# LED_array_-_interface_v1_3.net
KiCad netlist of a schematic drawn in EAGLE
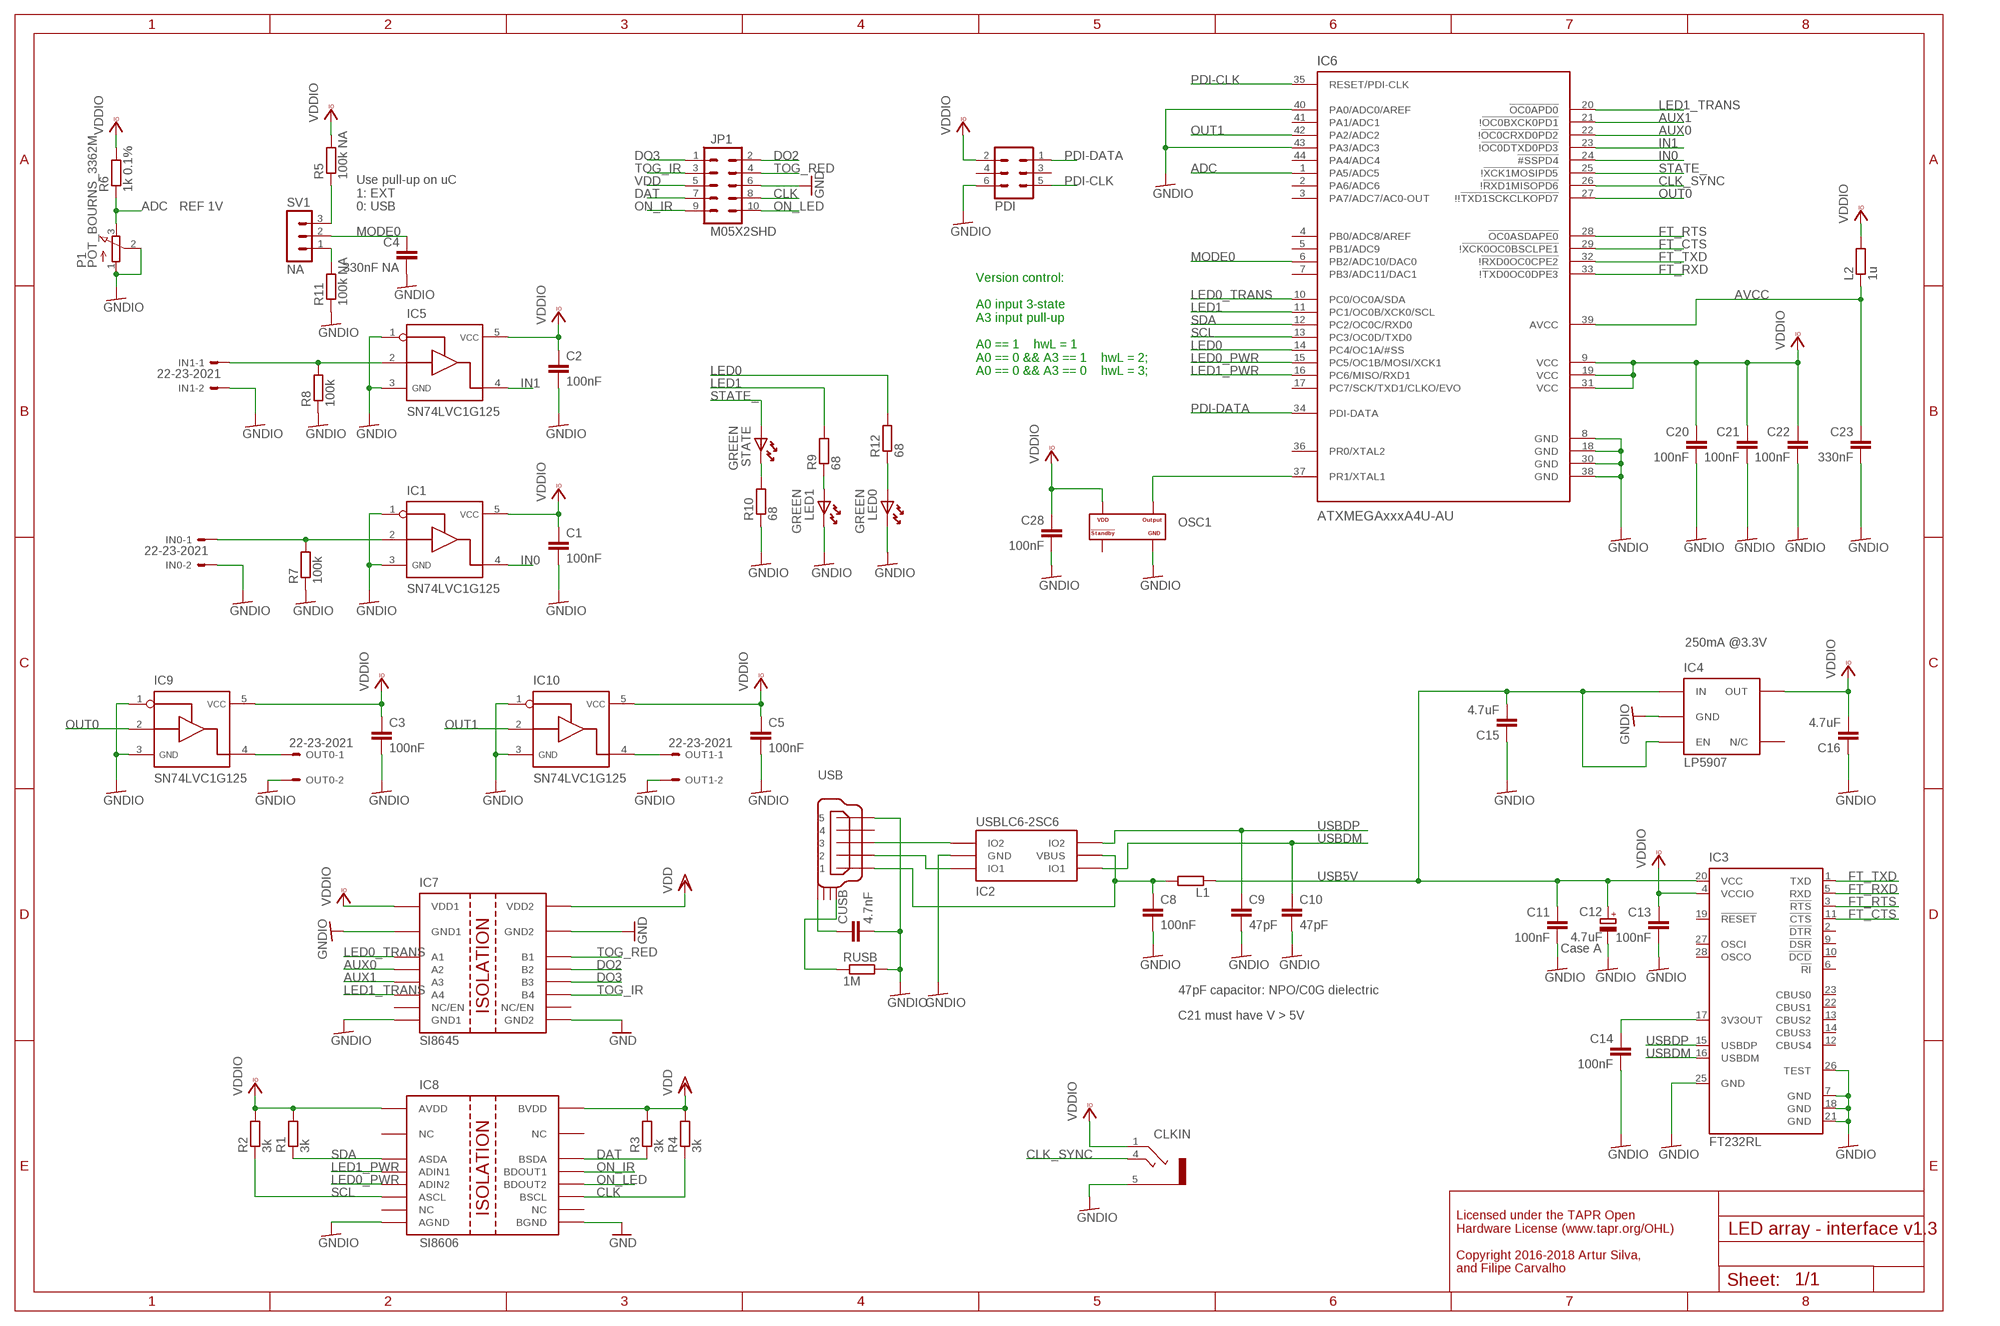
[diagram p0: schematic, sheet 1]

(export (version "E")
  (design (tool "Eeschema 10.0.6"))
  (components
    (comp (ref "C1")
      (value "100nF")
      (footprint "eagle-import:C0402")
      (libsource (lib "eagle-import") (part "C-EUC0402"))
    )
    (comp (ref "C2")
      (value "100nF")
      (footprint "eagle-import:C0402")
      (libsource (lib "eagle-import") (part "C-EUC0402"))
    )
    (comp (ref "C3")
      (value "100nF")
      (footprint "eagle-import:C0402")
      (libsource (lib "eagle-import") (part "C-EUC0402"))
    )
    (comp (ref "C4")
      (value "330nF NA")
      (footprint "eagle-import:C0402")
      (libsource (lib "eagle-import") (part "C-EUC0402"))
    )
    (comp (ref "C5")
      (value "100nF")
      (footprint "eagle-import:C0402")
      (libsource (lib "eagle-import") (part "C-EUC0402"))
    )
    (comp (ref "C8")
      (value "100nF")
      (footprint "eagle-import:C0402")
      (libsource (lib "eagle-import") (part "C-EUC0402"))
    )
    (comp (ref "C9")
      (value "47pF")
      (footprint "eagle-import:C0402")
      (libsource (lib "eagle-import") (part "C-EUC0402"))
    )
    (comp (ref "C10")
      (value "47pF")
      (footprint "eagle-import:C0402")
      (libsource (lib "eagle-import") (part "C-EUC0402"))
    )
    (comp (ref "C11")
      (value "100nF")
      (footprint "eagle-import:C0402")
      (libsource (lib "eagle-import") (part "C-EUC0402"))
    )
    (comp (ref "C12")
      (value "4.7uF")
      (footprint "eagle-import:A_3216-18W")
      (libsource (lib "eagle-import") (part "CPOL-EUA/3216-18W"))
    )
    (comp (ref "C13")
      (value "100nF")
      (footprint "eagle-import:C0402")
      (libsource (lib "eagle-import") (part "C-EUC0402"))
    )
    (comp (ref "C14")
      (value "100nF")
      (footprint "eagle-import:C0402")
      (libsource (lib "eagle-import") (part "C-EUC0402"))
    )
    (comp (ref "C15")
      (value "4.7uF")
      (footprint "eagle-import:C0402")
      (libsource (lib "eagle-import") (part "C-EUC0402"))
    )
    (comp (ref "C16")
      (value "4.7uF")
      (footprint "eagle-import:C0402")
      (libsource (lib "eagle-import") (part "C-EUC0402"))
    )
    (comp (ref "C20")
      (value "100nF")
      (footprint "eagle-import:C0402")
      (libsource (lib "eagle-import") (part "C-EUC0402"))
    )
    (comp (ref "C21")
      (value "100nF")
      (footprint "eagle-import:C0402")
      (libsource (lib "eagle-import") (part "C-EUC0402"))
    )
    (comp (ref "C22")
      (value "100nF")
      (footprint "eagle-import:C0402")
      (libsource (lib "eagle-import") (part "C-EUC0402"))
    )
    (comp (ref "C23")
      (value "330nF")
      (footprint "eagle-import:C0402")
      (libsource (lib "eagle-import") (part "C-EUC0402"))
    )
    (comp (ref "C28")
      (value "100nF")
      (footprint "eagle-import:C0402")
      (libsource (lib "eagle-import") (part "C-EUC0402"))
    )
    (comp (ref "CLKIN")
      (value "STEREO_JACK")
      (footprint "eagle-import:35RASMT2BHNTRX")
      (libsource (lib "eagle-import") (part "STEREO_JACK"))
    )
    (comp (ref "CUSB")
      (value "4.7nF")
      (footprint "eagle-import:C0402")
      (libsource (lib "eagle-import") (part "C-EUC0402"))
    )
    (comp (ref "IC1")
      (value "SN74LVC1G125")
      (footprint "eagle-import:SOT23-5")
      (libsource (lib "eagle-import") (part "SN74LVC1G125"))
    )
    (comp (ref "IC2")
      (value "USBLC6-2SC6")
      (footprint "eagle-import:SOT23-6L")
      (libsource (lib "eagle-import") (part "USBLC6-2"))
    )
    (comp (ref "IC3")
      (value "FT232RL")
      (footprint "eagle-import:SSOP28")
      (libsource (lib "eagle-import") (part "FT232RL"))
    )
    (comp (ref "IC4")
      (value "LP5907")
      (footprint "eagle-import:TSOT23-5")
      (libsource (lib "eagle-import") (part "TLV700XX"))
    )
    (comp (ref "IC5")
      (value "SN74LVC1G125")
      (footprint "eagle-import:SOT23-5")
      (libsource (lib "eagle-import") (part "SN74LVC1G125"))
    )
    (comp (ref "IC6")
      (value "ATXMEGAxxxA4U-AU")
      (footprint "eagle-import:QFP80P1200X1200X120-44N")
      (libsource (lib "eagle-import") (part "AT-XMEGA-XXA4-AU"))
    )
    (comp (ref "IC7")
      (value "SI8645")
      (footprint "eagle-import:NSOIC-16")
      (libsource (lib "eagle-import") (part "SI8645"))
    )
    (comp (ref "IC8")
      (value "SI8606")
      (footprint "eagle-import:NSOIC-16")
      (libsource (lib "eagle-import") (part "SI8606"))
    )
    (comp (ref "IC9")
      (value "SN74LVC1G125")
      (footprint "eagle-import:SOT23-5")
      (libsource (lib "eagle-import") (part "SN74LVC1G125"))
    )
    (comp (ref "IC10")
      (value "SN74LVC1G125")
      (footprint "eagle-import:SOT23-5")
      (libsource (lib "eagle-import") (part "SN74LVC1G125"))
    )
    (comp (ref "IN0")
      (value "22-23-2021")
      (footprint "eagle-import:22-23-2021")
      (fields (field (name "MF") "MOLEX"))
      (libsource (lib "eagle-import") (part "22-23-2021"))
    )
    (comp (ref "IN1")
      (value "22-23-2021")
      (footprint "eagle-import:22-23-2021")
      (fields (field (name "MF") "MOLEX"))
      (libsource (lib "eagle-import") (part "22-23-2021"))
    )
    (comp (ref "JP1")
      (value "M05X2SHD")
      (footprint "eagle-import:2X5-SHROUDED")
      (libsource (lib "eagle-import") (part "M05X2SHD"))
    )
    (comp (ref "L1")
      (value "???")
      (footprint "eagle-import:R0805")
      (libsource (lib "eagle-import") (part "R-EU_R0805"))
    )
    (comp (ref "L2")
      (value "1u")
      (footprint "eagle-import:R0805")
      (libsource (lib "eagle-import") (part "R-EU_R0805"))
    )
    (comp (ref "LED0")
      (value "GREEN")
      (footprint "eagle-import:LED_HAND")
      (libsource (lib "eagle-import") (part "LEDHAND"))
    )
    (comp (ref "LED1")
      (value "GREEN")
      (footprint "eagle-import:LED_HAND")
      (libsource (lib "eagle-import") (part "LEDHAND"))
    )
    (comp (ref "OSC1")
      (value "OSCILLATOR")
      (footprint "eagle-import:OSCILLATOR_3.2X2.5")
      (libsource (lib "eagle-import") (part "OSCILLATOR"))
    )
    (comp (ref "OUT0")
      (value "22-23-2021")
      (footprint "eagle-import:22-23-2021")
      (fields (field (name "MF") "MOLEX"))
      (libsource (lib "eagle-import") (part "22-23-2021"))
    )
    (comp (ref "OUT1")
      (value "22-23-2021")
      (footprint "eagle-import:22-23-2021")
      (fields (field (name "MF") "MOLEX"))
      (libsource (lib "eagle-import") (part "22-23-2021"))
    )
    (comp (ref "P1")
      (value "POT_BOURNS_3362M")
      (footprint "eagle-import:POT_BOURNS_3362M")
      (libsource (lib "eagle-import") (part "POT_BOURNS_3362M"))
    )
    (comp (ref "PDI")
      (value "MA03-2")
      (footprint "eagle-import:MA03-2")
      (libsource (lib "eagle-import") (part "MA03-2"))
    )
    (comp (ref "R1")
      (value "3k")
      (footprint "eagle-import:R0402")
      (libsource (lib "eagle-import") (part "R-EU_R0402"))
    )
    (comp (ref "R2")
      (value "3k")
      (footprint "eagle-import:R0402")
      (libsource (lib "eagle-import") (part "R-EU_R0402"))
    )
    (comp (ref "R3")
      (value "3k")
      (footprint "eagle-import:R0402")
      (libsource (lib "eagle-import") (part "R-EU_R0402"))
    )
    (comp (ref "R4")
      (value "3k")
      (footprint "eagle-import:R0402")
      (libsource (lib "eagle-import") (part "R-EU_R0402"))
    )
    (comp (ref "R5")
      (value "100k NA")
      (footprint "eagle-import:R0402")
      (libsource (lib "eagle-import") (part "R-EU_R0402"))
    )
    (comp (ref "R6")
      (value "1k 0.1%")
      (footprint "eagle-import:R0402")
      (libsource (lib "eagle-import") (part "R-EU_R0402"))
    )
    (comp (ref "R7")
      (value "100k")
      (footprint "eagle-import:R0402")
      (libsource (lib "eagle-import") (part "R-EU_R0402"))
    )
    (comp (ref "R8")
      (value "100k")
      (footprint "eagle-import:R0402")
      (libsource (lib "eagle-import") (part "R-EU_R0402"))
    )
    (comp (ref "R9")
      (value "68")
      (footprint "eagle-import:R0402")
      (libsource (lib "eagle-import") (part "R-EU_R0402"))
    )
    (comp (ref "R10")
      (value "68")
      (footprint "eagle-import:R0402")
      (libsource (lib "eagle-import") (part "R-EU_R0402"))
    )
    (comp (ref "R11")
      (value "100k NA")
      (footprint "eagle-import:R0402")
      (libsource (lib "eagle-import") (part "R-EU_R0402"))
    )
    (comp (ref "R12")
      (value "68")
      (footprint "eagle-import:R0402")
      (libsource (lib "eagle-import") (part "R-EU_R0402"))
    )
    (comp (ref "RUSB")
      (value "1M")
      (footprint "eagle-import:R0603")
      (libsource (lib "eagle-import") (part "R-EU_R0603"))
    )
    (comp (ref "STATE")
      (value "GREEN")
      (footprint "eagle-import:LED_HAND")
      (libsource (lib "eagle-import") (part "LEDHAND"))
    )
    (comp (ref "SV1")
      (value "NA")
      (footprint "eagle-import:MA03-1")
      (libsource (lib "eagle-import") (part "MA03-1"))
    )
    (comp (ref "USB")
      (value "USB_MINI_B")
      (footprint "eagle-import:240-0002-1")
      (libsource (lib "eagle-import") (part "USB_MINI_B"))
    )
  )
  (nets
    (net (code "1") (name "/ADC") (class "Default")
      (node (ref "IC6") (pin "1") (pinfunction "PA5/ADC5_1") (pintype "bidirectional"))
      (node (ref "P1") (pin "3") (pinfunction "E_3") (pintype "passive"))
      (node (ref "R6") (pin "1") (pinfunction "1_1") (pintype "passive"))
    )
    (net (code "2") (name "/AUX0") (class "Default")
      (node (ref "IC6") (pin "22") (pinfunction "~OC0CRXD0PD2_22") (pintype "bidirectional"))
      (node (ref "IC7") (pin "4") (pinfunction "A2_4") (pintype "bidirectional"))
    )
    (net (code "3") (name "/AUX1") (class "Default")
      (node (ref "IC6") (pin "21") (pinfunction "~OC0BXCK0PD1_21") (pintype "bidirectional"))
      (node (ref "IC7") (pin "5") (pinfunction "A3_5") (pintype "bidirectional"))
    )
    (net (code "4") (name "/AVCC") (class "Default")
      (node (ref "C23") (pin "1") (pinfunction "1_1") (pintype "passive"))
      (node (ref "IC6") (pin "39") (pinfunction "AVCC_39") (pintype "power_in"))
      (node (ref "L2") (pin "1") (pinfunction "1_1") (pintype "passive"))
    )
    (net (code "5") (name "/CLK") (class "Default")
      (node (ref "IC8") (pin "11") (pinfunction "BSCL_11") (pintype "bidirectional"))
      (node (ref "JP1") (pin "8") (pinfunction "8_8") (pintype "passive"))
      (node (ref "R4") (pin "1") (pinfunction "1_1") (pintype "passive"))
    )
    (net (code "6") (name "/CLK_SYNC") (class "Default")
      (node (ref "CLKIN") (pin "4") (pinfunction "4_4") (pintype "passive"))
      (node (ref "IC6") (pin "26") (pinfunction "~RXD1MISOPD6_26") (pintype "bidirectional"))
    )
    (net (code "7") (name "/DAT") (class "Default")
      (node (ref "IC8") (pin "14") (pinfunction "BSDA_14") (pintype "bidirectional"))
      (node (ref "JP1") (pin "7") (pinfunction "7_7") (pintype "passive"))
      (node (ref "R3") (pin "1") (pinfunction "1_1") (pintype "passive"))
    )
    (net (code "8") (name "/DO2") (class "Default")
      (node (ref "IC7") (pin "13") (pinfunction "B2_13") (pintype "bidirectional"))
      (node (ref "JP1") (pin "2") (pinfunction "2_2") (pintype "passive"))
    )
    (net (code "9") (name "/DO3") (class "Default")
      (node (ref "IC7") (pin "12") (pinfunction "B3_12") (pintype "bidirectional"))
      (node (ref "JP1") (pin "1") (pinfunction "1_1") (pintype "passive"))
    )
    (net (code "10") (name "/FT_CTS") (class "Default")
      (node (ref "IC3") (pin "11") (pinfunction "~{CTS}_11") (pintype "input"))
      (node (ref "IC6") (pin "29") (pinfunction "~XCK0OC0BSCLPE1_29") (pintype "bidirectional"))
    )
    (net (code "11") (name "/FT_RTS") (class "Default")
      (node (ref "IC3") (pin "3") (pinfunction "~{RTS}_3") (pintype "output"))
      (node (ref "IC6") (pin "28") (pinfunction "~{OC0ASDAPE0}_28") (pintype "bidirectional"))
    )
    (net (code "12") (name "/FT_RXD") (class "Default")
      (node (ref "IC3") (pin "5") (pinfunction "RXD_5") (pintype "input"))
      (node (ref "IC6") (pin "33") (pinfunction "~TXD0OC0DPE3_33") (pintype "bidirectional"))
    )
    (net (code "13") (name "/FT_TXD") (class "Default")
      (node (ref "IC3") (pin "1") (pinfunction "TXD_1") (pintype "output"))
      (node (ref "IC6") (pin "32") (pinfunction "~RXD0OC0CPE2_32") (pintype "bidirectional"))
    )
    (net (code "14") (name "/IN0") (class "Default")
      (node (ref "IC1") (pin "4") (pinfunction "P$4_4") (pintype "bidirectional"))
      (node (ref "IC6") (pin "24") (pinfunction "~{#SSPD4}_24") (pintype "bidirectional"))
    )
    (net (code "15") (name "/IN1") (class "Default")
      (node (ref "IC5") (pin "4") (pinfunction "P$4_4") (pintype "bidirectional"))
      (node (ref "IC6") (pin "23") (pinfunction "~OC0DTXD0PD3_23") (pintype "bidirectional"))
    )
    (net (code "16") (name "/LED0") (class "Default")
      (node (ref "IC6") (pin "14") (pinfunction "PC4/OC1A/#SS_14") (pintype "bidirectional"))
      (node (ref "R12") (pin "2") (pinfunction "2_2") (pintype "passive"))
    )
    (net (code "17") (name "/LED0_PWR") (class "Default")
      (node (ref "IC6") (pin "15") (pinfunction "PC5/OC1B/MOSI/XCK1_15") (pintype "bidirectional"))
      (node (ref "IC8") (pin "5") (pinfunction "ADIN2_5") (pintype "bidirectional"))
    )
    (net (code "18") (name "/LED0_TRANS") (class "Default")
      (node (ref "IC6") (pin "10") (pinfunction "PC0/OC0A/SDA_10") (pintype "bidirectional"))
      (node (ref "IC7") (pin "3") (pinfunction "A1_3") (pintype "bidirectional"))
    )
    (net (code "19") (name "/LED1") (class "Default")
      (node (ref "IC6") (pin "11") (pinfunction "PC1/OC0B/XCK0/SCL_11") (pintype "bidirectional"))
      (node (ref "R9") (pin "2") (pinfunction "2_2") (pintype "passive"))
    )
    (net (code "20") (name "/LED1_PWR") (class "Default")
      (node (ref "IC6") (pin "16") (pinfunction "PC6/MISO/RXD1_16") (pintype "bidirectional"))
      (node (ref "IC8") (pin "4") (pinfunction "ADIN1_4") (pintype "bidirectional"))
    )
    (net (code "21") (name "/LED1_TRANS") (class "Default")
      (node (ref "IC6") (pin "20") (pinfunction "~{OC0APD0}_20") (pintype "bidirectional"))
      (node (ref "IC7") (pin "6") (pinfunction "A4_6") (pintype "bidirectional"))
    )
    (net (code "22") (name "/MODE0") (class "Default")
      (node (ref "C4") (pin "1") (pinfunction "1_1") (pintype "passive"))
      (node (ref "IC6") (pin "6") (pinfunction "PB2/ADC10/DAC0_6") (pintype "bidirectional"))
      (node (ref "SV1") (pin "2") (pinfunction "2_2") (pintype "passive"))
    )
    (net (code "23") (name "/ON_IR") (class "Default")
      (node (ref "IC8") (pin "13") (pinfunction "BDOUT1_13") (pintype "bidirectional"))
      (node (ref "JP1") (pin "9") (pinfunction "9_9") (pintype "passive"))
    )
    (net (code "24") (name "/ON_LED") (class "Default")
      (node (ref "IC8") (pin "12") (pinfunction "BDOUT2_12") (pintype "bidirectional"))
      (node (ref "JP1") (pin "10") (pinfunction "10_10") (pintype "passive"))
    )
    (net (code "25") (name "/OUT0") (class "Default")
      (node (ref "IC6") (pin "27") (pinfunction "~~{TXD1SCKCLKOPD7}_27") (pintype "bidirectional"))
      (node (ref "IC9") (pin "2") (pinfunction "P$2_2") (pintype "bidirectional"))
    )
    (net (code "26") (name "/OUT1") (class "Default")
      (node (ref "IC10") (pin "2") (pinfunction "P$2_2") (pintype "bidirectional"))
      (node (ref "IC6") (pin "42") (pinfunction "PA2/ADC2_42") (pintype "bidirectional"))
    )
    (net (code "27") (name "/PDI-CLK") (class "Default")
      (node (ref "IC6") (pin "35") (pinfunction "RESET/PDI-CLK_35") (pintype "input"))
      (node (ref "PDI") (pin "5") (pinfunction "5_5") (pintype "passive"))
    )
    (net (code "28") (name "/PDI-DATA") (class "Default")
      (node (ref "IC6") (pin "34") (pinfunction "PDI-DATA_34") (pintype "bidirectional"))
      (node (ref "PDI") (pin "1") (pinfunction "1_1") (pintype "passive"))
    )
    (net (code "29") (name "/SCL") (class "Default")
      (node (ref "IC6") (pin "13") (pinfunction "PC3/OC0D/TXD0_13") (pintype "bidirectional"))
      (node (ref "IC8") (pin "6") (pinfunction "ASCL_6") (pintype "bidirectional"))
      (node (ref "R2") (pin "1") (pinfunction "1_1") (pintype "passive"))
    )
    (net (code "30") (name "/SDA") (class "Default")
      (node (ref "IC6") (pin "12") (pinfunction "PC2/OC0C/RXD0_12") (pintype "bidirectional"))
      (node (ref "IC8") (pin "3") (pinfunction "ASDA_3") (pintype "bidirectional"))
      (node (ref "R1") (pin "1") (pinfunction "1_1") (pintype "passive"))
    )
    (net (code "31") (name "/STATE_") (class "Default")
      (node (ref "IC6") (pin "25") (pinfunction "~XCK1MOSIPD5_25") (pintype "bidirectional"))
      (node (ref "STATE") (pin "A") (pinfunction "A_A") (pintype "bidirectional"))
    )
    (net (code "32") (name "/TOG_IR") (class "Default")
      (node (ref "IC7") (pin "11") (pinfunction "B4_11") (pintype "bidirectional"))
      (node (ref "JP1") (pin "3") (pinfunction "3_3") (pintype "passive"))
    )
    (net (code "33") (name "/TOG_RED") (class "Default")
      (node (ref "IC7") (pin "14") (pinfunction "B1_14") (pintype "bidirectional"))
      (node (ref "JP1") (pin "4") (pinfunction "4_4") (pintype "passive"))
    )
    (net (code "34") (name "/USB5V") (class "Default")
      (node (ref "C11") (pin "1") (pinfunction "1_1") (pintype "passive"))
      (node (ref "C12") (pin "+") (pinfunction "+_+") (pintype "passive"))
      (node (ref "C15") (pin "2") (pinfunction "2_2") (pintype "passive"))
      (node (ref "IC3") (pin "20") (pinfunction "VCC_20") (pintype "power_in"))
      (node (ref "IC4") (pin "1") (pinfunction "IN_1") (pintype "bidirectional"))
      (node (ref "IC4") (pin "3") (pinfunction "EN_3") (pintype "bidirectional"))
      (node (ref "L1") (pin "1") (pinfunction "1_1") (pintype "passive"))
    )
    (net (code "35") (name "/USBDM") (class "Default")
      (node (ref "C10") (pin "1") (pinfunction "1_1") (pintype "passive"))
      (node (ref "IC2") (pin "P$6") (pinfunction "IO1_P$6") (pintype "bidirectional"))
      (node (ref "IC3") (pin "16") (pinfunction "USBDM_16") (pintype "bidirectional"))
    )
    (net (code "36") (name "/USBDP") (class "Default")
      (node (ref "C9") (pin "1") (pinfunction "1_1") (pintype "passive"))
      (node (ref "IC2") (pin "P$4") (pinfunction "IO2_P$4") (pintype "bidirectional"))
      (node (ref "IC3") (pin "15") (pinfunction "USBDP_15") (pintype "bidirectional"))
    )
    (net (code "37") (name "GND") (class "Default")
      (node (ref "IC7") (pin "15") (pinfunction "GND2_15") (pintype "bidirectional"))
      (node (ref "IC7") (pin "9") (pinfunction "GND2_9") (pintype "bidirectional"))
      (node (ref "IC8") (pin "9") (pinfunction "BGND_9") (pintype "bidirectional"))
      (node (ref "JP1") (pin "6") (pinfunction "6_6") (pintype "passive"))
    )
    (net (code "38") (name "GNDIO") (class "Default")
      (node (ref "C1") (pin "2") (pinfunction "2_2") (pintype "passive"))
      (node (ref "C10") (pin "2") (pinfunction "2_2") (pintype "passive"))
      (node (ref "C11") (pin "2") (pinfunction "2_2") (pintype "passive"))
      (node (ref "C12") (pin "-") (pinfunction "-_-") (pintype "passive"))
      (node (ref "C13") (pin "2") (pinfunction "2_2") (pintype "passive"))
      (node (ref "C14") (pin "2") (pinfunction "2_2") (pintype "passive"))
      (node (ref "C15") (pin "1") (pinfunction "1_1") (pintype "passive"))
      (node (ref "C16") (pin "1") (pinfunction "1_1") (pintype "passive"))
      (node (ref "C2") (pin "2") (pinfunction "2_2") (pintype "passive"))
      (node (ref "C20") (pin "2") (pinfunction "2_2") (pintype "passive"))
      (node (ref "C21") (pin "2") (pinfunction "2_2") (pintype "passive"))
      (node (ref "C22") (pin "2") (pinfunction "2_2") (pintype "passive"))
      (node (ref "C23") (pin "2") (pinfunction "2_2") (pintype "passive"))
      (node (ref "C28") (pin "2") (pinfunction "2_2") (pintype "passive"))
      (node (ref "C3") (pin "2") (pinfunction "2_2") (pintype "passive"))
      (node (ref "C4") (pin "2") (pinfunction "2_2") (pintype "passive"))
      (node (ref "C5") (pin "2") (pinfunction "2_2") (pintype "passive"))
      (node (ref "C8") (pin "2") (pinfunction "2_2") (pintype "passive"))
      (node (ref "C9") (pin "2") (pinfunction "2_2") (pintype "passive"))
      (node (ref "CLKIN") (pin "5") (pinfunction "5_5") (pintype "passive"))
      (node (ref "CUSB") (pin "2") (pinfunction "2_2") (pintype "passive"))
      (node (ref "IC1") (pin "1") (pinfunction "P$1_1") (pintype "bidirectional"))
      (node (ref "IC1") (pin "3") (pinfunction "P$3_3") (pintype "bidirectional"))
      (node (ref "IC10") (pin "1") (pinfunction "P$1_1") (pintype "bidirectional"))
      (node (ref "IC10") (pin "3") (pinfunction "P$3_3") (pintype "bidirectional"))
      (node (ref "IC2") (pin "P$2") (pinfunction "GND_P$2") (pintype "bidirectional"))
      (node (ref "IC3") (pin "18") (pinfunction "GND_18") (pintype "power_in"))
      (node (ref "IC3") (pin "21") (pinfunction "GND_21") (pintype "power_in"))
      (node (ref "IC3") (pin "25") (pinfunction "GND_25") (pintype "power_in"))
      (node (ref "IC3") (pin "26") (pinfunction "TEST_26") (pintype "input"))
      (node (ref "IC3") (pin "7") (pinfunction "GND_7") (pintype "power_in"))
      (node (ref "IC4") (pin "2") (pinfunction "GND_2") (pintype "bidirectional"))
      (node (ref "IC5") (pin "1") (pinfunction "P$1_1") (pintype "bidirectional"))
      (node (ref "IC5") (pin "3") (pinfunction "P$3_3") (pintype "bidirectional"))
      (node (ref "IC6") (pin "18") (pinfunction "GND_18") (pintype "power_in"))
      (node (ref "IC6") (pin "30") (pinfunction "GND_30") (pintype "power_in"))
      (node (ref "IC6") (pin "38") (pinfunction "GND_38") (pintype "power_in"))
      (node (ref "IC6") (pin "40") (pinfunction "PA0/ADC0/AREF_40") (pintype "bidirectional"))
      (node (ref "IC6") (pin "43") (pinfunction "PA3/ADC3_43") (pintype "bidirectional"))
      (node (ref "IC6") (pin "8") (pinfunction "GND_8") (pintype "power_in"))
      (node (ref "IC7") (pin "2") (pinfunction "GND1_2") (pintype "bidirectional"))
      (node (ref "IC7") (pin "8") (pinfunction "GND1_8") (pintype "bidirectional"))
      (node (ref "IC8") (pin "8") (pinfunction "AGND_8") (pintype "bidirectional"))
      (node (ref "IC9") (pin "1") (pinfunction "P$1_1") (pintype "bidirectional"))
      (node (ref "IC9") (pin "3") (pinfunction "P$3_3") (pintype "bidirectional"))
      (node (ref "IN0") (pin "2") (pinfunction "S_2") (pintype "passive"))
      (node (ref "IN1") (pin "2") (pinfunction "S_2") (pintype "passive"))
      (node (ref "LED0") (pin "K") (pinfunction "K_K") (pintype "bidirectional"))
      (node (ref "LED1") (pin "K") (pinfunction "K_K") (pintype "bidirectional"))
      (node (ref "OSC1") (pin "P$2") (pinfunction "GND_P$2") (pintype "passive"))
      (node (ref "OUT0") (pin "2") (pinfunction "S_2") (pintype "passive"))
      (node (ref "OUT1") (pin "2") (pinfunction "S_2") (pintype "passive"))
      (node (ref "P1") (pin "1") (pinfunction "A_1") (pintype "passive"))
      (node (ref "P1") (pin "2") (pinfunction "S_2") (pintype "passive"))
      (node (ref "PDI") (pin "6") (pinfunction "6_6") (pintype "passive"))
      (node (ref "R10") (pin "1") (pinfunction "1_1") (pintype "passive"))
      (node (ref "R11") (pin "1") (pinfunction "1_1") (pintype "passive"))
      (node (ref "R7") (pin "1") (pinfunction "1_1") (pintype "passive"))
      (node (ref "R8") (pin "1") (pinfunction "1_1") (pintype "passive"))
      (node (ref "RUSB") (pin "2") (pinfunction "2_2") (pintype "passive"))
      (node (ref "USB") (pin "P$5") (pinfunction "5_P$5") (pintype "bidirectional"))
    )
    (net (code "39") (name "Net-(IC1-P$2)") (class "Default")
      (node (ref "IC1") (pin "2") (pinfunction "P$2_2") (pintype "bidirectional"))
      (node (ref "IN0") (pin "1") (pinfunction "S_1") (pintype "passive"))
      (node (ref "R7") (pin "2") (pinfunction "2_2") (pintype "passive"))
    )
    (net (code "40") (name "Net-(IC2-VBUS)") (class "Default")
      (node (ref "C8") (pin "1") (pinfunction "1_1") (pintype "passive"))
      (node (ref "IC2") (pin "P$5") (pinfunction "VBUS_P$5") (pintype "bidirectional"))
      (node (ref "L1") (pin "2") (pinfunction "2_2") (pintype "passive"))
      (node (ref "USB") (pin "P$1") (pinfunction "1_P$1") (pintype "bidirectional"))
    )
    (net (code "41") (name "Net-(IC3-3V3OUT)") (class "Default")
      (node (ref "C14") (pin "1") (pinfunction "1_1") (pintype "passive"))
      (node (ref "IC3") (pin "17") (pinfunction "3V3OUT_17") (pintype "output"))
    )
    (net (code "42") (name "Net-(IC5-P$2)") (class "Default")
      (node (ref "IC5") (pin "2") (pinfunction "P$2_2") (pintype "bidirectional"))
      (node (ref "IN1") (pin "1") (pinfunction "S_1") (pintype "passive"))
      (node (ref "R8") (pin "2") (pinfunction "2_2") (pintype "passive"))
    )
    (net (code "43") (name "Net-(IC6-PR1{slash}XTAL1)") (class "Default")
      (node (ref "IC6") (pin "37") (pinfunction "PR1/XTAL1_37") (pintype "bidirectional"))
      (node (ref "OSC1") (pin "P$3") (pinfunction "OUTPUT_P$3") (pintype "passive"))
    )
    (net (code "44") (name "Net-(IC9-P$4)") (class "Default")
      (node (ref "IC9") (pin "4") (pinfunction "P$4_4") (pintype "bidirectional"))
      (node (ref "OUT0") (pin "1") (pinfunction "S_1") (pintype "passive"))
    )
    (net (code "45") (name "Net-(IC10-P$4)") (class "Default")
      (node (ref "IC10") (pin "4") (pinfunction "P$4_4") (pintype "bidirectional"))
      (node (ref "OUT1") (pin "1") (pinfunction "S_1") (pintype "passive"))
    )
    (net (code "46") (name "Net-(LED0-PadA)") (class "Default")
      (node (ref "LED0") (pin "A") (pinfunction "A_A") (pintype "bidirectional"))
      (node (ref "R12") (pin "1") (pinfunction "1_1") (pintype "passive"))
    )
    (net (code "47") (name "Net-(LED1-PadA)") (class "Default")
      (node (ref "LED1") (pin "A") (pinfunction "A_A") (pintype "bidirectional"))
      (node (ref "R9") (pin "1") (pinfunction "1_1") (pintype "passive"))
    )
    (net (code "48") (name "Net-(R5-Pad1)") (class "Default")
      (node (ref "R5") (pin "1") (pinfunction "1_1") (pintype "passive"))
      (node (ref "SV1") (pin "3") (pinfunction "3_3") (pintype "passive"))
    )
    (net (code "49") (name "Net-(R10-Pad2)") (class "Default")
      (node (ref "R10") (pin "2") (pinfunction "2_2") (pintype "passive"))
      (node (ref "STATE") (pin "K") (pinfunction "K_K") (pintype "bidirectional"))
    )
    (net (code "50") (name "Net-(R11-Pad2)") (class "Default")
      (node (ref "R11") (pin "2") (pinfunction "2_2") (pintype "passive"))
      (node (ref "SV1") (pin "1") (pinfunction "1_1") (pintype "passive"))
    )
    (net (code "51") (name "Net-(USB-2)") (class "Default")
      (node (ref "IC2") (pin "P$1") (pinfunction "IO1_P$1") (pintype "bidirectional"))
      (node (ref "USB") (pin "P$2") (pinfunction "2_P$2") (pintype "bidirectional"))
    )
    (net (code "52") (name "Net-(USB-3)") (class "Default")
      (node (ref "IC2") (pin "P$3") (pinfunction "IO2_P$3") (pintype "bidirectional"))
      (node (ref "USB") (pin "P$3") (pinfunction "3_P$3") (pintype "bidirectional"))
    )
    (net (code "53") (name "Net-(USB-P$1)") (class "Default")
      (node (ref "RUSB") (pin "1") (pinfunction "1_1") (pintype "passive"))
      (node (ref "USB") (pin "SHIELD_1") (pinfunction "P$1_SHIELD_1") (pintype "bidirectional"))
    )
    (net (code "54") (name "Net-(USB-P$4)") (class "Default")
      (node (ref "CUSB") (pin "1") (pinfunction "1_1") (pintype "passive"))
      (node (ref "USB") (pin "SHIELD_4") (pinfunction "P$4_SHIELD_4") (pintype "bidirectional"))
    )
    (net (code "55") (name "VDD") (class "Default")
      (node (ref "IC7") (pin "16") (pinfunction "VDD2_16") (pintype "bidirectional"))
      (node (ref "IC8") (pin "16") (pinfunction "BVDD_16") (pintype "bidirectional"))
      (node (ref "JP1") (pin "5") (pinfunction "5_5") (pintype "passive"))
      (node (ref "R3") (pin "2") (pinfunction "2_2") (pintype "passive"))
      (node (ref "R4") (pin "2") (pinfunction "2_2") (pintype "passive"))
    )
    (net (code "56") (name "VDDIO") (class "Default")
      (node (ref "C1") (pin "1") (pinfunction "1_1") (pintype "passive"))
      (node (ref "C13") (pin "1") (pinfunction "1_1") (pintype "passive"))
      (node (ref "C16") (pin "2") (pinfunction "2_2") (pintype "passive"))
      (node (ref "C2") (pin "1") (pinfunction "1_1") (pintype "passive"))
      (node (ref "C20") (pin "1") (pinfunction "1_1") (pintype "passive"))
      (node (ref "C21") (pin "1") (pinfunction "1_1") (pintype "passive"))
      (node (ref "C22") (pin "1") (pinfunction "1_1") (pintype "passive"))
      (node (ref "C28") (pin "1") (pinfunction "1_1") (pintype "passive"))
      (node (ref "C3") (pin "1") (pinfunction "1_1") (pintype "passive"))
      (node (ref "C5") (pin "1") (pinfunction "1_1") (pintype "passive"))
      (node (ref "CLKIN") (pin "1") (pinfunction "1_1") (pintype "passive"))
      (node (ref "IC1") (pin "5") (pinfunction "P$5_5") (pintype "bidirectional"))
      (node (ref "IC10") (pin "5") (pinfunction "P$5_5") (pintype "bidirectional"))
      (node (ref "IC3") (pin "4") (pinfunction "VCCIO_4") (pintype "power_in"))
      (node (ref "IC4") (pin "5") (pinfunction "OUT_5") (pintype "bidirectional"))
      (node (ref "IC5") (pin "5") (pinfunction "P$5_5") (pintype "bidirectional"))
      (node (ref "IC6") (pin "19") (pinfunction "VCC_19") (pintype "power_in"))
      (node (ref "IC6") (pin "31") (pinfunction "VCC_31") (pintype "power_in"))
      (node (ref "IC6") (pin "9") (pinfunction "VCC_9") (pintype "power_in"))
      (node (ref "IC7") (pin "1") (pinfunction "VDD1_1") (pintype "bidirectional"))
      (node (ref "IC8") (pin "1") (pinfunction "AVDD_1") (pintype "bidirectional"))
      (node (ref "IC9") (pin "5") (pinfunction "P$5_5") (pintype "bidirectional"))
      (node (ref "L2") (pin "2") (pinfunction "2_2") (pintype "passive"))
      (node (ref "OSC1") (pin "P$4") (pinfunction "VDD_P$4") (pintype "passive"))
      (node (ref "PDI") (pin "2") (pinfunction "2_2") (pintype "passive"))
      (node (ref "R1") (pin "2") (pinfunction "2_2") (pintype "passive"))
      (node (ref "R2") (pin "2") (pinfunction "2_2") (pintype "passive"))
      (node (ref "R5") (pin "2") (pinfunction "2_2") (pintype "passive"))
      (node (ref "R6") (pin "2") (pinfunction "2_2") (pintype "passive"))
    )
    (net (code "57") (name "unconnected-(IC3-CBUS0-Pad23)") (class "Default")
      (node (ref "IC3") (pin "23") (pinfunction "CBUS0_23") (pintype "bidirectional"))
    )
    (net (code "58") (name "unconnected-(IC3-CBUS1-Pad22)") (class "Default")
      (node (ref "IC3") (pin "22") (pinfunction "CBUS1_22") (pintype "bidirectional"))
    )
    (net (code "59") (name "unconnected-(IC3-CBUS2-Pad13)") (class "Default")
      (node (ref "IC3") (pin "13") (pinfunction "CBUS2_13") (pintype "bidirectional"))
    )
    (net (code "60") (name "unconnected-(IC3-CBUS3-Pad14)") (class "Default")
      (node (ref "IC3") (pin "14") (pinfunction "CBUS3_14") (pintype "bidirectional"))
    )
    (net (code "61") (name "unconnected-(IC3-CBUS4-Pad12)") (class "Default")
      (node (ref "IC3") (pin "12") (pinfunction "CBUS4_12") (pintype "bidirectional"))
    )
    (net (code "62") (name "unconnected-(IC3-OSCI-Pad27)") (class "Default")
      (node (ref "IC3") (pin "27") (pinfunction "OSCI_27") (pintype "input"))
    )
    (net (code "63") (name "unconnected-(IC3-OSCO-Pad28)") (class "Default")
      (node (ref "IC3") (pin "28") (pinfunction "OSCO_28") (pintype "output"))
    )
    (net (code "64") (name "unconnected-(IC3-~{DCD}-Pad10)") (class "Default")
      (node (ref "IC3") (pin "10") (pinfunction "~{DCD}_10") (pintype "input"))
    )
    (net (code "65") (name "unconnected-(IC3-~{DSR}-Pad9)") (class "Default")
      (node (ref "IC3") (pin "9") (pinfunction "~{DSR}_9") (pintype "input"))
    )
    (net (code "66") (name "unconnected-(IC3-~{DTR}-Pad2)") (class "Default")
      (node (ref "IC3") (pin "2") (pinfunction "~{DTR}_2") (pintype "output"))
    )
    (net (code "67") (name "unconnected-(IC3-~{RESET}-Pad19)") (class "Default")
      (node (ref "IC3") (pin "19") (pinfunction "~{RESET}_19") (pintype "input"))
    )
    (net (code "68") (name "unconnected-(IC3-~{RI}-Pad6)") (class "Default")
      (node (ref "IC3") (pin "6") (pinfunction "~{RI}_6") (pintype "input"))
    )
    (net (code "69") (name "unconnected-(IC4-N{slash}C-Pad4)") (class "Default")
      (node (ref "IC4") (pin "4") (pinfunction "N/C_4") (pintype "bidirectional"))
    )
    (net (code "70") (name "unconnected-(IC6-PA1{slash}ADC1-Pad41)") (class "Default")
      (node (ref "IC6") (pin "41") (pinfunction "PA1/ADC1_41") (pintype "bidirectional"))
    )
    (net (code "71") (name "unconnected-(IC6-PA4{slash}ADC4-Pad44)") (class "Default")
      (node (ref "IC6") (pin "44") (pinfunction "PA4/ADC4_44") (pintype "bidirectional"))
    )
    (net (code "72") (name "unconnected-(IC6-PA6{slash}ADC6-Pad2)") (class "Default")
      (node (ref "IC6") (pin "2") (pinfunction "PA6/ADC6_2") (pintype "bidirectional"))
    )
    (net (code "73") (name "unconnected-(IC6-PA7{slash}ADC7{slash}AC0-OUT-Pad3)") (class "Default")
      (node (ref "IC6") (pin "3") (pinfunction "PA7/ADC7/AC0-OUT_3") (pintype "bidirectional"))
    )
    (net (code "74") (name "unconnected-(IC6-PB0{slash}ADC8{slash}AREF-Pad4)") (class "Default")
      (node (ref "IC6") (pin "4") (pinfunction "PB0/ADC8/AREF_4") (pintype "bidirectional"))
    )
    (net (code "75") (name "unconnected-(IC6-PB1{slash}ADC9-Pad5)") (class "Default")
      (node (ref "IC6") (pin "5") (pinfunction "PB1/ADC9_5") (pintype "bidirectional"))
    )
    (net (code "76") (name "unconnected-(IC6-PB3{slash}ADC11{slash}DAC1-Pad7)") (class "Default")
      (node (ref "IC6") (pin "7") (pinfunction "PB3/ADC11/DAC1_7") (pintype "bidirectional"))
    )
    (net (code "77") (name "unconnected-(IC6-PC7{slash}SCK{slash}TXD1{slash}CLKO{slash}EVO-Pad17)") (class "Default")
      (node (ref "IC6") (pin "17") (pinfunction "PC7/SCK/TXD1/CLKO/EVO_17") (pintype "bidirectional"))
    )
    (net (code "78") (name "unconnected-(IC6-PR0{slash}XTAL2-Pad36)") (class "Default")
      (node (ref "IC6") (pin "36") (pinfunction "PR0/XTAL2_36") (pintype "bidirectional"))
    )
    (net (code "79") (name "unconnected-(IC7-NC{slash}EN-Pad7)") (class "Default")
      (node (ref "IC7") (pin "7") (pinfunction "NC/EN_7") (pintype "bidirectional"))
    )
    (net (code "80") (name "unconnected-(IC7-NC{slash}EN-Pad10)") (class "Default")
      (node (ref "IC7") (pin "10") (pinfunction "NC/EN_10") (pintype "bidirectional"))
    )
    (net (code "81") (name "unconnected-(IC8-NC-Pad2)") (class "Default")
      (node (ref "IC8") (pin "2") (pinfunction "NC_2") (pintype "bidirectional"))
    )
    (net (code "82") (name "unconnected-(IC8-NC-Pad7)") (class "Default")
      (node (ref "IC8") (pin "7") (pinfunction "NC_7") (pintype "bidirectional"))
    )
    (net (code "83") (name "unconnected-(IC8-NC-Pad10)") (class "Default")
      (node (ref "IC8") (pin "10") (pinfunction "NC_10") (pintype "bidirectional"))
    )
    (net (code "84") (name "unconnected-(IC8-NC-Pad15)") (class "Default")
      (node (ref "IC8") (pin "15") (pinfunction "NC_15") (pintype "bidirectional"))
    )
    (net (code "85") (name "unconnected-(OSC1-STANDBY#-PadP$1)") (class "Default")
      (node (ref "OSC1") (pin "P$1") (pinfunction "STANDBY#_P$1") (pintype "passive"))
    )
    (net (code "86") (name "unconnected-(PDI-Pad3)") (class "Default")
      (node (ref "PDI") (pin "3") (pinfunction "3_3") (pintype "passive"))
    )
    (net (code "87") (name "unconnected-(PDI-Pad4)") (class "Default")
      (node (ref "PDI") (pin "4") (pinfunction "4_4") (pintype "passive"))
    )
    (net (code "88") (name "unconnected-(USB-4-PadP$4)") (class "Default")
      (node (ref "USB") (pin "P$4") (pinfunction "4_P$4") (pintype "bidirectional"))
    )
    (net (code "89") (name "unconnected-(USB-P$2-PadSHIELD_2)") (class "Default")
      (node (ref "USB") (pin "SHIELD_2") (pinfunction "P$2_SHIELD_2") (pintype "bidirectional"))
    )
    (net (code "90") (name "unconnected-(USB-P$3-PadSHIELD_3)") (class "Default")
      (node (ref "USB") (pin "SHIELD_3") (pinfunction "P$3_SHIELD_3") (pintype "bidirectional"))
    )
  )
)
